# HIVE_BOARD_MCU.net
KiCad netlist of a schematic drawn in Altium Designer
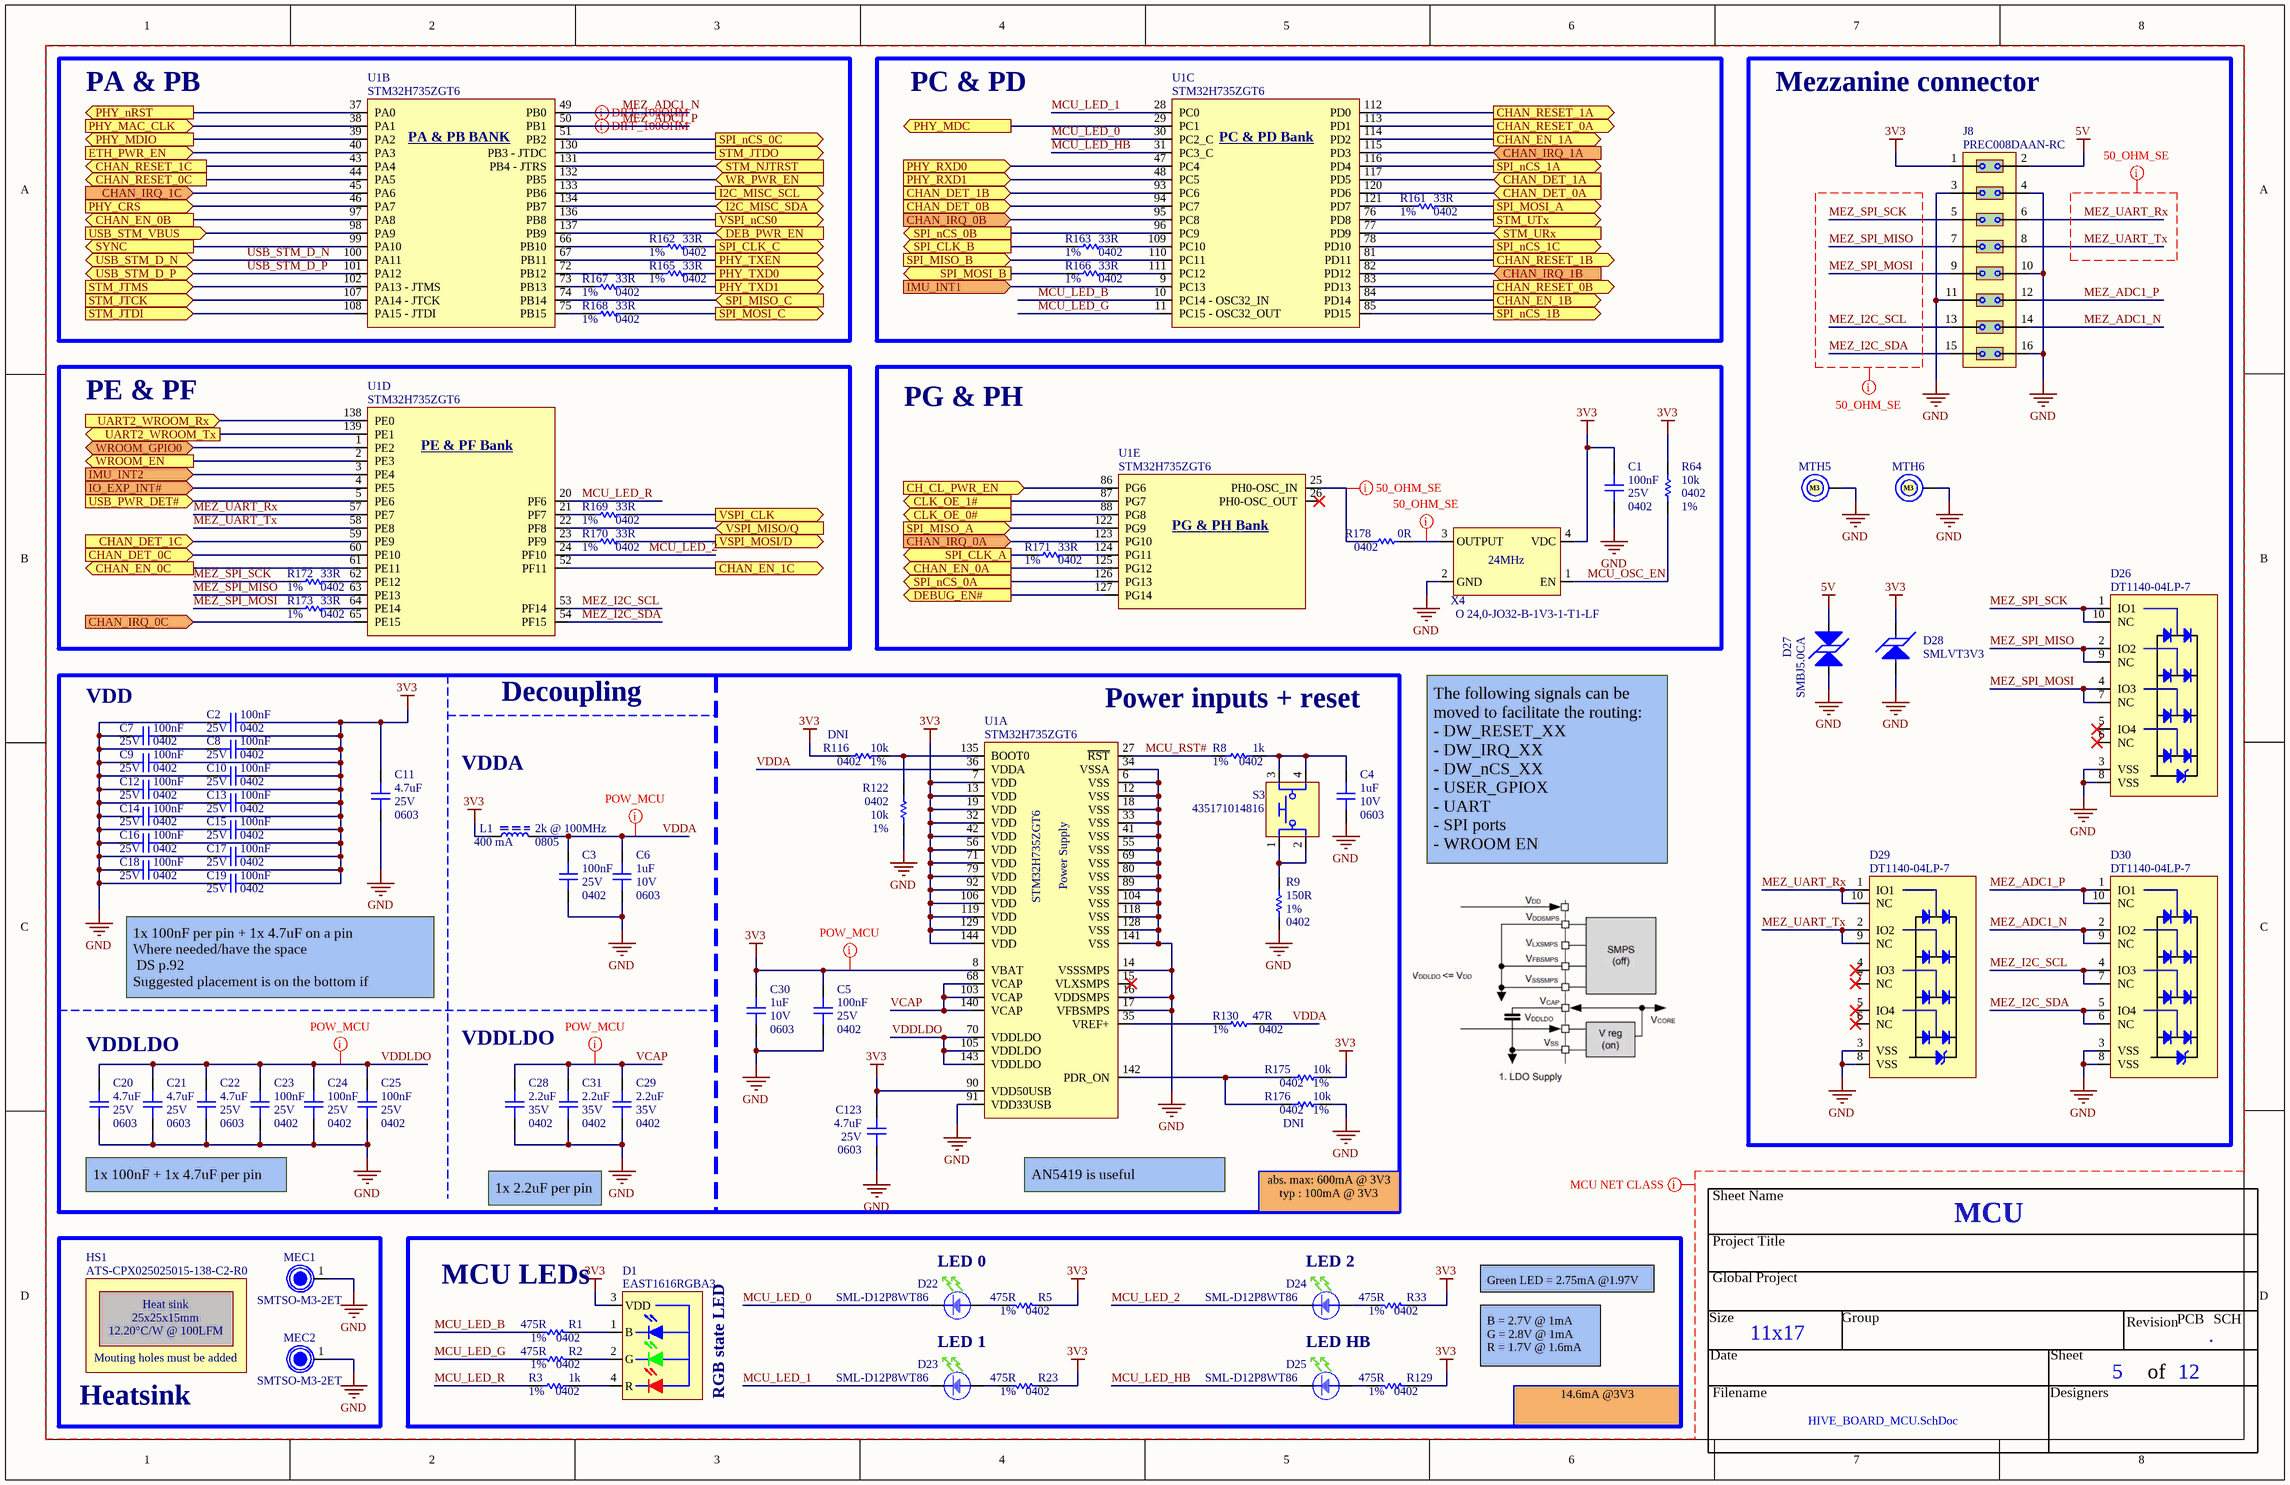
[diagram p0: HIVE_BOARD_MCU.SchDoc]

(export (version "E")
  (design (tool "Eeschema 10.0.6"))
  (components
    (comp (ref "C1")
      (value "100nF")
      (footprint "CAP_CER_0402")
      (description "CAP - CER 0.1µF 10% 25V X7R - 0402")
      (fields
        (field (name "TOLERANCE") "10%")
        (field (name "PACKAGE") "0402")
        (field (name "VOLTAGE RATING") "25V")
        (field (name "Comment") "CGA2B3X7R1E104K050BB")
        (field (name "CREATEDBY/DATE") "Nicolas Roy 2018-11-07")
        (field (name "VERIFIEDBY") "Nicolas V. (2019-01-22)")
      )
      (libsource (lib "GRAMS_MASTER_LIB") (part "CAP_CER_CGA2B3X7R1E104K050BB"))
    )
    (comp (ref "C2")
      (value "100nF")
      (footprint "CAP_CER_0402")
      (description "CAP - CER 0.1µF 10% 25V X7R - 0402")
      (fields
        (field (name "TOLERANCE") "10%")
        (field (name "PACKAGE") "0402")
        (field (name "VOLTAGE RATING") "25V")
        (field (name "Comment") "CGA2B3X7R1E104K050BB")
        (field (name "CREATEDBY/DATE") "Nicolas Roy 2018-11-07")
        (field (name "VERIFIEDBY") "Nicolas V. (2019-01-22)")
      )
      (libsource (lib "GRAMS_MASTER_LIB") (part "CAP_CER_CGA2B3X7R1E104K050BB"))
    )
    (comp (ref "C3")
      (value "100nF")
      (footprint "CAP_CER_0402")
      (description "CAP - CER 0.1µF 10% 25V X7R - 0402")
      (fields
        (field (name "TOLERANCE") "10%")
        (field (name "PACKAGE") "0402")
        (field (name "VOLTAGE RATING") "25V")
        (field (name "Comment") "CGA2B3X7R1E104K050BB")
        (field (name "CREATEDBY/DATE") "Nicolas Roy 2018-11-07")
        (field (name "VERIFIEDBY") "Nicolas V. (2019-01-22)")
      )
      (libsource (lib "GRAMS_MASTER_LIB") (part "CAP_CER_CGA2B3X7R1E104K050BB"))
    )
    (comp (ref "C4")
      (value "1uF")
      (footprint "CAP_CER_0603")
      (description "CAP - CER 1uF 10V 10% X5R - 0603")
      (fields
        (field (name "TOLERANCE") "10%")
        (field (name "PACKAGE") "0603")
        (field (name "VOLTAGE RATING") "10V")
        (field (name "Comment") "C0603C105K8PACTU")
        (field (name "CREATEDBY/DATE") "Hubert Dube - 21/07/20")
        (field (name "VERIFIEDBY") "Louis-Daniel Gaulin - 21/07/20")
      )
      (libsource (lib "SWARMUS_LIB") (part "CAP_CER_C0603C105K8PACTU"))
    )
    (comp (ref "C5")
      (value "100nF")
      (footprint "CAP_CER_0402")
      (description "CAP - CER 0.1µF 10% 25V X7R - 0402")
      (fields
        (field (name "TOLERANCE") "10%")
        (field (name "PACKAGE") "0402")
        (field (name "VOLTAGE RATING") "25V")
        (field (name "Comment") "CGA2B3X7R1E104K050BB")
        (field (name "CREATEDBY/DATE") "Nicolas Roy 2018-11-07")
        (field (name "VERIFIEDBY") "Nicolas V. (2019-01-22)")
      )
      (libsource (lib "GRAMS_MASTER_LIB") (part "CAP_CER_CGA2B3X7R1E104K050BB"))
    )
    (comp (ref "C6")
      (value "1uF")
      (footprint "CAP_CER_0603")
      (description "CAP - CER 1uF 10V 10% X5R - 0603")
      (fields
        (field (name "TOLERANCE") "10%")
        (field (name "PACKAGE") "0603")
        (field (name "VOLTAGE RATING") "10V")
        (field (name "Comment") "C0603C105K8PACTU")
        (field (name "CREATEDBY/DATE") "Hubert Dube - 21/07/20")
        (field (name "VERIFIEDBY") "Louis-Daniel Gaulin - 21/07/20")
      )
      (libsource (lib "SWARMUS_LIB") (part "CAP_CER_C0603C105K8PACTU"))
    )
    (comp (ref "C7")
      (value "100nF")
      (footprint "CAP_CER_0402")
      (description "CAP - CER 0.1µF 10% 25V X7R - 0402")
      (fields
        (field (name "TOLERANCE") "10%")
        (field (name "PACKAGE") "0402")
        (field (name "VOLTAGE RATING") "25V")
        (field (name "Comment") "CGA2B3X7R1E104K050BB")
        (field (name "CREATEDBY/DATE") "Nicolas Roy 2018-11-07")
        (field (name "VERIFIEDBY") "Nicolas V. (2019-01-22)")
      )
      (libsource (lib "GRAMS_MASTER_LIB") (part "CAP_CER_CGA2B3X7R1E104K050BB"))
    )
    (comp (ref "C8")
      (value "100nF")
      (footprint "CAP_CER_0402")
      (description "CAP - CER 0.1µF 10% 25V X7R - 0402")
      (fields
        (field (name "TOLERANCE") "10%")
        (field (name "PACKAGE") "0402")
        (field (name "VOLTAGE RATING") "25V")
        (field (name "Comment") "CGA2B3X7R1E104K050BB")
        (field (name "CREATEDBY/DATE") "Nicolas Roy 2018-11-07")
        (field (name "VERIFIEDBY") "Nicolas V. (2019-01-22)")
      )
      (libsource (lib "GRAMS_MASTER_LIB") (part "CAP_CER_CGA2B3X7R1E104K050BB"))
    )
    (comp (ref "C9")
      (value "100nF")
      (footprint "CAP_CER_0402")
      (description "CAP - CER 0.1µF 10% 25V X7R - 0402")
      (fields
        (field (name "TOLERANCE") "10%")
        (field (name "PACKAGE") "0402")
        (field (name "VOLTAGE RATING") "25V")
        (field (name "Comment") "CGA2B3X7R1E104K050BB")
        (field (name "CREATEDBY/DATE") "Nicolas Roy 2018-11-07")
        (field (name "VERIFIEDBY") "Nicolas V. (2019-01-22)")
      )
      (libsource (lib "GRAMS_MASTER_LIB") (part "CAP_CER_CGA2B3X7R1E104K050BB"))
    )
    (comp (ref "C10")
      (value "100nF")
      (footprint "CAP_CER_0402")
      (description "CAP - CER 0.1µF 10% 25V X7R - 0402")
      (fields
        (field (name "TOLERANCE") "10%")
        (field (name "PACKAGE") "0402")
        (field (name "VOLTAGE RATING") "25V")
        (field (name "Comment") "CGA2B3X7R1E104K050BB")
        (field (name "CREATEDBY/DATE") "Nicolas Roy 2018-11-07")
        (field (name "VERIFIEDBY") "Nicolas V. (2019-01-22)")
      )
      (libsource (lib "GRAMS_MASTER_LIB") (part "CAP_CER_CGA2B3X7R1E104K050BB"))
    )
    (comp (ref "C11")
      (value "4.7uF")
      (footprint "CAP_CER_0603")
      (description "CAP - CER 4.7µF 20% 25V X5R - 0603")
      (fields
        (field (name "TOLERANCE") "20%")
        (field (name "PACKAGE") "0603")
        (field (name "VOLTAGE RATING") "25V")
        (field (name "Comment") "CL10A475MA8NQNC")
        (field (name "CREATEDBY/DATE") "Nicolas Roy 2018-11-21")
        (field (name "VERIFIEDBY") "Nicolas V. (2019-01-22)")
      )
      (libsource (lib "GRAMS_MASTER_LIB") (part "CAP_CER_CL10A475MA8NQNC"))
    )
    (comp (ref "C12")
      (value "100nF")
      (footprint "CAP_CER_0402")
      (description "CAP - CER 0.1µF 10% 25V X7R - 0402")
      (fields
        (field (name "TOLERANCE") "10%")
        (field (name "PACKAGE") "0402")
        (field (name "VOLTAGE RATING") "25V")
        (field (name "Comment") "CGA2B3X7R1E104K050BB")
        (field (name "CREATEDBY/DATE") "Nicolas Roy 2018-11-07")
        (field (name "VERIFIEDBY") "Nicolas V. (2019-01-22)")
      )
      (libsource (lib "GRAMS_MASTER_LIB") (part "CAP_CER_CGA2B3X7R1E104K050BB"))
    )
    (comp (ref "C13")
      (value "100nF")
      (footprint "CAP_CER_0402")
      (description "CAP - CER 0.1µF 10% 25V X7R - 0402")
      (fields
        (field (name "TOLERANCE") "10%")
        (field (name "PACKAGE") "0402")
        (field (name "VOLTAGE RATING") "25V")
        (field (name "Comment") "CGA2B3X7R1E104K050BB")
        (field (name "CREATEDBY/DATE") "Nicolas Roy 2018-11-07")
        (field (name "VERIFIEDBY") "Nicolas V. (2019-01-22)")
      )
      (libsource (lib "GRAMS_MASTER_LIB") (part "CAP_CER_CGA2B3X7R1E104K050BB"))
    )
    (comp (ref "C14")
      (value "100nF")
      (footprint "CAP_CER_0402")
      (description "CAP - CER 0.1µF 10% 25V X7R - 0402")
      (fields
        (field (name "TOLERANCE") "10%")
        (field (name "PACKAGE") "0402")
        (field (name "VOLTAGE RATING") "25V")
        (field (name "Comment") "CGA2B3X7R1E104K050BB")
        (field (name "CREATEDBY/DATE") "Nicolas Roy 2018-11-07")
        (field (name "VERIFIEDBY") "Nicolas V. (2019-01-22)")
      )
      (libsource (lib "GRAMS_MASTER_LIB") (part "CAP_CER_CGA2B3X7R1E104K050BB"))
    )
    (comp (ref "C15")
      (value "100nF")
      (footprint "CAP_CER_0402")
      (description "CAP - CER 0.1µF 10% 25V X7R - 0402")
      (fields
        (field (name "TOLERANCE") "10%")
        (field (name "PACKAGE") "0402")
        (field (name "VOLTAGE RATING") "25V")
        (field (name "Comment") "CGA2B3X7R1E104K050BB")
        (field (name "CREATEDBY/DATE") "Nicolas Roy 2018-11-07")
        (field (name "VERIFIEDBY") "Nicolas V. (2019-01-22)")
      )
      (libsource (lib "GRAMS_MASTER_LIB") (part "CAP_CER_CGA2B3X7R1E104K050BB"))
    )
    (comp (ref "C16")
      (value "100nF")
      (footprint "CAP_CER_0402")
      (description "CAP - CER 0.1µF 10% 25V X7R - 0402")
      (fields
        (field (name "TOLERANCE") "10%")
        (field (name "PACKAGE") "0402")
        (field (name "VOLTAGE RATING") "25V")
        (field (name "Comment") "CGA2B3X7R1E104K050BB")
        (field (name "CREATEDBY/DATE") "Nicolas Roy 2018-11-07")
        (field (name "VERIFIEDBY") "Nicolas V. (2019-01-22)")
      )
      (libsource (lib "GRAMS_MASTER_LIB") (part "CAP_CER_CGA2B3X7R1E104K050BB"))
    )
    (comp (ref "C17")
      (value "100nF")
      (footprint "CAP_CER_0402")
      (description "CAP - CER 0.1µF 10% 25V X7R - 0402")
      (fields
        (field (name "TOLERANCE") "10%")
        (field (name "PACKAGE") "0402")
        (field (name "VOLTAGE RATING") "25V")
        (field (name "Comment") "CGA2B3X7R1E104K050BB")
        (field (name "CREATEDBY/DATE") "Nicolas Roy 2018-11-07")
        (field (name "VERIFIEDBY") "Nicolas V. (2019-01-22)")
      )
      (libsource (lib "GRAMS_MASTER_LIB") (part "CAP_CER_CGA2B3X7R1E104K050BB"))
    )
    (comp (ref "C18")
      (value "100nF")
      (footprint "CAP_CER_0402")
      (description "CAP - CER 0.1µF 10% 25V X7R - 0402")
      (fields
        (field (name "TOLERANCE") "10%")
        (field (name "PACKAGE") "0402")
        (field (name "VOLTAGE RATING") "25V")
        (field (name "Comment") "CGA2B3X7R1E104K050BB")
        (field (name "CREATEDBY/DATE") "Nicolas Roy 2018-11-07")
        (field (name "VERIFIEDBY") "Nicolas V. (2019-01-22)")
      )
      (libsource (lib "GRAMS_MASTER_LIB") (part "CAP_CER_CGA2B3X7R1E104K050BB"))
    )
    (comp (ref "C19")
      (value "100nF")
      (footprint "CAP_CER_0402")
      (description "CAP - CER 0.1µF 10% 25V X7R - 0402")
      (fields
        (field (name "TOLERANCE") "10%")
        (field (name "PACKAGE") "0402")
        (field (name "VOLTAGE RATING") "25V")
        (field (name "Comment") "CGA2B3X7R1E104K050BB")
        (field (name "CREATEDBY/DATE") "Nicolas Roy 2018-11-07")
        (field (name "VERIFIEDBY") "Nicolas V. (2019-01-22)")
      )
      (libsource (lib "GRAMS_MASTER_LIB") (part "CAP_CER_CGA2B3X7R1E104K050BB"))
    )
    (comp (ref "C20")
      (value "4.7uF")
      (footprint "CAP_CER_0603")
      (description "CAP - CER 4.7µF 20% 25V X5R - 0603")
      (fields
        (field (name "TOLERANCE") "20%")
        (field (name "PACKAGE") "0603")
        (field (name "VOLTAGE RATING") "25V")
        (field (name "Comment") "CL10A475MA8NQNC")
        (field (name "CREATEDBY/DATE") "Nicolas Roy 2018-11-21")
        (field (name "VERIFIEDBY") "Nicolas V. (2019-01-22)")
      )
      (libsource (lib "GRAMS_MASTER_LIB") (part "CAP_CER_CL10A475MA8NQNC"))
    )
    (comp (ref "C21")
      (value "4.7uF")
      (footprint "CAP_CER_0603")
      (description "CAP - CER 4.7µF 20% 25V X5R - 0603")
      (fields
        (field (name "TOLERANCE") "20%")
        (field (name "PACKAGE") "0603")
        (field (name "VOLTAGE RATING") "25V")
        (field (name "Comment") "CL10A475MA8NQNC")
        (field (name "CREATEDBY/DATE") "Nicolas Roy 2018-11-21")
        (field (name "VERIFIEDBY") "Nicolas V. (2019-01-22)")
      )
      (libsource (lib "GRAMS_MASTER_LIB") (part "CAP_CER_CL10A475MA8NQNC"))
    )
    (comp (ref "C22")
      (value "4.7uF")
      (footprint "CAP_CER_0603")
      (description "CAP - CER 4.7µF 20% 25V X5R - 0603")
      (fields
        (field (name "TOLERANCE") "20%")
        (field (name "PACKAGE") "0603")
        (field (name "VOLTAGE RATING") "25V")
        (field (name "Comment") "CL10A475MA8NQNC")
        (field (name "CREATEDBY/DATE") "Nicolas Roy 2018-11-21")
        (field (name "VERIFIEDBY") "Nicolas V. (2019-01-22)")
      )
      (libsource (lib "GRAMS_MASTER_LIB") (part "CAP_CER_CL10A475MA8NQNC"))
    )
    (comp (ref "C23")
      (value "100nF")
      (footprint "CAP_CER_0402")
      (description "CAP - CER 0.1µF 10% 25V X7R - 0402")
      (fields
        (field (name "TOLERANCE") "10%")
        (field (name "PACKAGE") "0402")
        (field (name "VOLTAGE RATING") "25V")
        (field (name "Comment") "CGA2B3X7R1E104K050BB")
        (field (name "CREATEDBY/DATE") "Nicolas Roy 2018-11-07")
        (field (name "VERIFIEDBY") "Nicolas V. (2019-01-22)")
      )
      (libsource (lib "GRAMS_MASTER_LIB") (part "CAP_CER_CGA2B3X7R1E104K050BB"))
    )
    (comp (ref "C24")
      (value "100nF")
      (footprint "CAP_CER_0402")
      (description "CAP - CER 0.1µF 10% 25V X7R - 0402")
      (fields
        (field (name "TOLERANCE") "10%")
        (field (name "PACKAGE") "0402")
        (field (name "VOLTAGE RATING") "25V")
        (field (name "Comment") "CGA2B3X7R1E104K050BB")
        (field (name "CREATEDBY/DATE") "Nicolas Roy 2018-11-07")
        (field (name "VERIFIEDBY") "Nicolas V. (2019-01-22)")
      )
      (libsource (lib "GRAMS_MASTER_LIB") (part "CAP_CER_CGA2B3X7R1E104K050BB"))
    )
    (comp (ref "C25")
      (value "100nF")
      (footprint "CAP_CER_0402")
      (description "CAP - CER 0.1µF 10% 25V X7R - 0402")
      (fields
        (field (name "TOLERANCE") "10%")
        (field (name "PACKAGE") "0402")
        (field (name "VOLTAGE RATING") "25V")
        (field (name "Comment") "CGA2B3X7R1E104K050BB")
        (field (name "CREATEDBY/DATE") "Nicolas Roy 2018-11-07")
        (field (name "VERIFIEDBY") "Nicolas V. (2019-01-22)")
      )
      (libsource (lib "GRAMS_MASTER_LIB") (part "CAP_CER_CGA2B3X7R1E104K050BB"))
    )
    (comp (ref "C28")
      (value "2.2uF")
      (footprint "CAP_CER_0402")
      (description "CAP - CER 2.2µF 10% 35V X5R - 0402")
      (fields
        (field (name "TOLERANCE") "10%")
        (field (name "PACKAGE") "0402")
        (field (name "VOLTAGE RATING") "35V")
        (field (name "Comment") "C1005X5R1V225K050BC")
        (field (name "CREATEDBY/DATE") "Nicolas Roy 2018-10-17")
        (field (name "VERIFIEDBY") "Caroline Paulin - 18 janv 2018")
      )
      (libsource (lib "GRAMS_MASTER_LIB") (part "CAP_CER_C1005X5R1V225K050BC"))
    )
    (comp (ref "C29")
      (value "2.2uF")
      (footprint "CAP_CER_0402")
      (description "CAP - CER 2.2µF 10% 35V X5R - 0402")
      (fields
        (field (name "TOLERANCE") "10%")
        (field (name "PACKAGE") "0402")
        (field (name "VOLTAGE RATING") "35V")
        (field (name "Comment") "C1005X5R1V225K050BC")
        (field (name "CREATEDBY/DATE") "Nicolas Roy 2018-10-17")
        (field (name "VERIFIEDBY") "Caroline Paulin - 18 janv 2018")
      )
      (libsource (lib "GRAMS_MASTER_LIB") (part "CAP_CER_C1005X5R1V225K050BC"))
    )
    (comp (ref "C30")
      (value "1uF")
      (footprint "CAP_CER_0603")
      (description "CAP - CER 1uF 10V 10% X5R - 0603")
      (fields
        (field (name "TOLERANCE") "10%")
        (field (name "PACKAGE") "0603")
        (field (name "VOLTAGE RATING") "10V")
        (field (name "Comment") "C0603C105K8PACTU")
        (field (name "CREATEDBY/DATE") "Hubert Dube - 21/07/20")
        (field (name "VERIFIEDBY") "Louis-Daniel Gaulin - 21/07/20")
      )
      (libsource (lib "SWARMUS_LIB") (part "CAP_CER_C0603C105K8PACTU"))
    )
    (comp (ref "C31")
      (value "2.2uF")
      (footprint "CAP_CER_0402")
      (description "CAP - CER 2.2µF 10% 35V X5R - 0402")
      (fields
        (field (name "TOLERANCE") "10%")
        (field (name "PACKAGE") "0402")
        (field (name "VOLTAGE RATING") "35V")
        (field (name "Comment") "C1005X5R1V225K050BC")
        (field (name "CREATEDBY/DATE") "Nicolas Roy 2018-10-17")
        (field (name "VERIFIEDBY") "Caroline Paulin - 18 janv 2018")
      )
      (libsource (lib "GRAMS_MASTER_LIB") (part "CAP_CER_C1005X5R1V225K050BC"))
    )
    (comp (ref "C123")
      (value "4.7uF")
      (footprint "CAP_CER_0603")
      (description "CAP - CER 4.7µF 20% 25V X5R - 0603")
      (fields
        (field (name "TOLERANCE") "20%")
        (field (name "PACKAGE") "0603")
        (field (name "VOLTAGE RATING") "25V")
        (field (name "Comment") "CL10A475MA8NQNC")
        (field (name "CREATEDBY/DATE") "Nicolas Roy 2018-11-21")
        (field (name "VERIFIEDBY") "Nicolas V. (2019-01-22)")
      )
      (libsource (lib "GRAMS_MASTER_LIB") (part "CAP_CER_CL10A475MA8NQNC"))
    )
    (comp (ref "D1")
      (value "EAST1616RGBA3")
      (footprint "DIO_EAST1616RGBA3")
      (fields
        (field (name "TOLERANCE") "±50ppm")
        (field (name "CREATEDBY/DATE") "Hubert Dube - 26/02/2021")
        (field (name "VERIFIEDBY") "PA + Hubert Dube - 19/03/2021")
      )
      (libsource (lib "SWARMUS_LIB") (part "DIO_EAST1616RGBA3"))
    )
    (comp (ref "D22")
      (value "SML-D12P8WT86")
      (footprint "LED_SML-D12P8WT86")
      (description "LED - GREEN DIFFUSED 0603 SMD - 0603")
      (fields
        (field (name "CREATEDBY/DATE") "Keven Deslandes - 2018/11/21")
        (field (name "VERIFIEDBY") "Caroline Paulin - 13 février 2019")
      )
      (libsource (lib "GRAMS_MASTER_LIB") (part "LED_SML-D12P8WT86"))
    )
    (comp (ref "D23")
      (value "SML-D12P8WT86")
      (footprint "LED_SML-D12P8WT86")
      (description "LED - GREEN DIFFUSED 0603 SMD - 0603")
      (fields
        (field (name "CREATEDBY/DATE") "Keven Deslandes - 2018/11/21")
        (field (name "VERIFIEDBY") "Caroline Paulin - 13 février 2019")
      )
      (libsource (lib "GRAMS_MASTER_LIB") (part "LED_SML-D12P8WT86"))
    )
    (comp (ref "D24")
      (value "SML-D12P8WT86")
      (footprint "LED_SML-D12P8WT86")
      (description "LED - GREEN DIFFUSED 0603 SMD - 0603")
      (fields
        (field (name "CREATEDBY/DATE") "Keven Deslandes - 2018/11/21")
        (field (name "VERIFIEDBY") "Caroline Paulin - 13 février 2019")
      )
      (libsource (lib "GRAMS_MASTER_LIB") (part "LED_SML-D12P8WT86"))
    )
    (comp (ref "D25")
      (value "SML-D12P8WT86")
      (footprint "LED_SML-D12P8WT86")
      (description "LED - GREEN DIFFUSED 0603 SMD - 0603")
      (fields
        (field (name "CREATEDBY/DATE") "Keven Deslandes - 2018/11/21")
        (field (name "VERIFIEDBY") "Caroline Paulin - 13 février 2019")
      )
      (libsource (lib "GRAMS_MASTER_LIB") (part "LED_SML-D12P8WT86"))
    )
    (comp (ref "D26")
      (value "DT1140-04LP-7")
      (footprint "TVS_DATA_DT1140-04LP-7")
      (description "TVS - DIODE 5.5V 10V - 10-UFDFN")
      (fields
        (field (name "CREATEDBY/DATE") "Joël Lemay 2019-11-20")
        (field (name "VERIFIEDBY") "C.Paulin - 21/11/2019")
      )
      (libsource (lib "GRAMS_MASTER_LIB") (part "TVS_DATA_DT1140-04LP-7"))
    )
    (comp (ref "D27")
      (value "SMBJ5.0CA")
      (footprint "TVS_PWR_SMBJ5.0CA")
      (description "TVS - BIDIR 5V 9.2V 600W - DO214AA")
      (fields
        (field (name "CREATEDBY/DATE") "Jonathan Bouchard - 2019-03-22")
        (field (name "VERIFIEDBY") "Nicolas V. (2019-05-06)")
      )
      (libsource (lib "GRAMS_MASTER_LIB") (part "TVS_PWR_SMBJ5.0CA"))
    )
    (comp (ref "D28")
      (value "SMLVT3V3")
      (footprint "TVS_POW_SMLVT3V3")
      (description "TVS - 3.3V 10.3V 600W - DO214AA")
      (fields
        (field (name "CREATEDBY/DATE") "Jonathan Bouchard - 2019-04-27")
        (field (name "VERIFIEDBY") "Nicolas V. (2019-05-06)")
      )
      (libsource (lib "GRAMS_MASTER_LIB") (part "TVS_POW_SMLVT3V3"))
    )
    (comp (ref "D29")
      (value "DT1140-04LP-7")
      (footprint "TVS_DATA_DT1140-04LP-7")
      (description "TVS - DIODE 5.5V 10V - 10-UFDFN")
      (fields
        (field (name "CREATEDBY/DATE") "Joël Lemay 2019-11-20")
        (field (name "VERIFIEDBY") "C.Paulin - 21/11/2019")
      )
      (libsource (lib "GRAMS_MASTER_LIB") (part "TVS_DATA_DT1140-04LP-7"))
    )
    (comp (ref "D30")
      (value "DT1140-04LP-7")
      (footprint "TVS_DATA_DT1140-04LP-7")
      (description "TVS - DIODE 5.5V 10V - 10-UFDFN")
      (fields
        (field (name "CREATEDBY/DATE") "Joël Lemay 2019-11-20")
        (field (name "VERIFIEDBY") "C.Paulin - 21/11/2019")
      )
      (libsource (lib "GRAMS_MASTER_LIB") (part "TVS_DATA_DT1140-04LP-7"))
    )
    (comp (ref "HS1")
      (value "ATS-CPX025025015-138-C2-R0")
      (footprint "THE_HS_ATS-CPX025025015-138-C2-R0_NOMH")
      (description "THE_HS - Heat Sink  25x25x15 mm - TH M3")
      (fields
        (field (name "CREATEDBY/DATE") "Philippe Arsenault/2021-04-08")
        (field (name "VERIFIEDBY") "Louis-Daniel Gaulin / 14-04-2021")
      )
      (libsource (lib "SWARMUS_LIB") (part "THE_HS_ATS-CPX025025015-138-C2-R0_NOMH"))
    )
    (comp (ref "J8")
      (value "PREC008DAAN-RC")
      (footprint "CON_HDR_PREC008DAAN-RC")
      (description "CON - Connector Header Through Hole 16 position 0.100\" (2.54mm)")
      (fields
        (field (name "VERIFIEDBY") "Philippe Arsenault/2021-03-25")
        (field (name "CREATEDBY/DATE") "Hubert Dube -  16/03/2021")
      )
      (libsource (lib "SWARMUS_LIB") (part "CON_HDR_PREC008DAAN-RC"))
    )
    (comp (ref "L1")
      (value "2k @ 100MHz")
      (footprint "FER_0805")
      (description "FER - FERRITE BEAD 2 KOHM @ 100 MHz 400 mA - 0805")
      (fields
        (field (name "CURRENT RATING") "400 mA")
        (field (name "PACKAGE") "0805")
        (field (name "Comment") "MMZ2012Y202BT000")
        (field (name "CREATEDBY/DATE") "Hubert Dube - 7/02/2021")
        (field (name "VERIFIEDBY") "Philippe Arsenault/ 2021-03-13")
      )
      (libsource (lib "SWARMUS_LIB") (part "FER_MMZ2012Y202BT000"))
    )
    (comp (ref "MEC1")
      (value "SMTSO-M3-2ET")
      (footprint "MEC_PEM_SMTSO-M3-2ET")
      (description "MEC- PEM SMD THREADED SPACER M3 - SMD")
      (fields
        (field (name "CREATEDBY/DATE") "Gabriel St-H./30-04-2019")
        (field (name "VERIFIEDBY") "Nicolas V. (2019-05-02)")
      )
      (libsource (lib "GRAMS_MASTER_LIB") (part "MEC_PEM_SMTSO-M3-2ET"))
    )
    (comp (ref "MEC2")
      (value "SMTSO-M3-2ET")
      (footprint "MEC_PEM_SMTSO-M3-2ET")
      (description "MEC- PEM SMD THREADED SPACER M3 - SMD")
      (fields
        (field (name "CREATEDBY/DATE") "Gabriel St-H./30-04-2019")
        (field (name "VERIFIEDBY") "Nicolas V. (2019-05-02)")
      )
      (libsource (lib "GRAMS_MASTER_LIB") (part "MEC_PEM_SMTSO-M3-2ET"))
    )
    (comp (ref "MTH5")
      (value "M3")
      (footprint "MTH_M3")
      (description "MTH - MOUNTING HOLE M3 PLATED - M3")
      (fields
        (field (name "CREATEDBY/DATE") "Jonathan Bouchard 2018-07-23")
        (field (name "VERIFIEDBY") "Arnaud Samson 23-07-18")
      )
      (libsource (lib "GRAMS_MASTER_LIB") (part "MTH_M3"))
    )
    (comp (ref "MTH6")
      (value "M3")
      (footprint "MTH_M3")
      (description "MTH - MOUNTING HOLE M3 PLATED - M3")
      (fields
        (field (name "CREATEDBY/DATE") "Jonathan Bouchard 2018-07-23")
        (field (name "VERIFIEDBY") "Arnaud Samson 23-07-18")
      )
      (libsource (lib "GRAMS_MASTER_LIB") (part "MTH_M3"))
    )
    (comp (ref "R1")
      (value "475R")
      (footprint "RES_0402")
      (description "RES - 475R 1% 1/10W- 0402")
      (fields
        (field (name "TOLERANCE") "1%")
        (field (name "PACKAGE") "0402")
        (field (name "Comment") "ERJ-2RKF4750X")
        (field (name "CREATEDBY/DATE") "Keven Deslandes 2018-10-17")
        (field (name "VERIFIEDBY") "Carolilne Paulin - 18/12/2018")
      )
      (libsource (lib "GRAMS_MASTER_LIB") (part "RES_ERJ-2RKF4750X"))
    )
    (comp (ref "R2")
      (value "475R")
      (footprint "RES_0402")
      (description "RES - 475R 1% 1/10W- 0402")
      (fields
        (field (name "TOLERANCE") "1%")
        (field (name "PACKAGE") "0402")
        (field (name "Comment") "ERJ-2RKF4750X")
        (field (name "CREATEDBY/DATE") "Keven Deslandes 2018-10-17")
        (field (name "VERIFIEDBY") "Carolilne Paulin - 18/12/2018")
      )
      (libsource (lib "GRAMS_MASTER_LIB") (part "RES_ERJ-2RKF4750X"))
    )
    (comp (ref "R3")
      (value "1k")
      (footprint "RES_0402")
      (description "RES - 1K OHM 1% 1/16W - 0402")
      (fields
        (field (name "TOLERANCE") "1%")
        (field (name "PACKAGE") "0402")
        (field (name "Comment") "RC0402FR-071KL")
        (field (name "CREATEDBY/DATE") "Jonathan Bouchard 2018-07-05")
        (field (name "VERIFIEDBY") "Arnaud Samson 16-07-18")
      )
      (libsource (lib "GRAMS_MASTER_LIB") (part "RES_RC0402FR-071KL"))
    )
    (comp (ref "R5")
      (value "475R")
      (footprint "RES_0402")
      (description "RES - 475R 1% 1/10W- 0402")
      (fields
        (field (name "TOLERANCE") "1%")
        (field (name "PACKAGE") "0402")
        (field (name "Comment") "ERJ-2RKF4750X")
        (field (name "CREATEDBY/DATE") "Keven Deslandes 2018-10-17")
        (field (name "VERIFIEDBY") "Carolilne Paulin - 18/12/2018")
      )
      (libsource (lib "GRAMS_MASTER_LIB") (part "RES_ERJ-2RKF4750X"))
    )
    (comp (ref "R8")
      (value "1k")
      (footprint "RES_0402")
      (description "RES - 1K OHM 1% 1/16W - 0402")
      (fields
        (field (name "TOLERANCE") "1%")
        (field (name "PACKAGE") "0402")
        (field (name "Comment") "RC0402FR-071KL")
        (field (name "CREATEDBY/DATE") "Jonathan Bouchard 2018-07-05")
        (field (name "VERIFIEDBY") "Arnaud Samson 16-07-18")
      )
      (libsource (lib "GRAMS_MASTER_LIB") (part "RES_RC0402FR-071KL"))
    )
    (comp (ref "R9")
      (value "150R")
      (footprint "RES_0402")
      (description "RES - 150R 1% 1/16W - 0402")
      (fields
        (field (name "TOLERANCE") "1%")
        (field (name "PACKAGE") "0402")
        (field (name "Comment") "RC0402FR-07150RL")
        (field (name "CREATEDBY/DATE") "Jonathan Bouchard 2019-03-25")
        (field (name "VERIFIEDBY") "Nicolas V. (2019-05-02)")
      )
      (libsource (lib "GRAMS_MASTER_LIB") (part "RES_RC0402FR-07150RL"))
    )
    (comp (ref "R23")
      (value "475R")
      (footprint "RES_0402")
      (description "RES - 475R 1% 1/10W- 0402")
      (fields
        (field (name "TOLERANCE") "1%")
        (field (name "PACKAGE") "0402")
        (field (name "Comment") "ERJ-2RKF4750X")
        (field (name "CREATEDBY/DATE") "Keven Deslandes 2018-10-17")
        (field (name "VERIFIEDBY") "Carolilne Paulin - 18/12/2018")
      )
      (libsource (lib "GRAMS_MASTER_LIB") (part "RES_ERJ-2RKF4750X"))
    )
    (comp (ref "R33")
      (value "475R")
      (footprint "RES_0402")
      (description "RES - 475R 1% 1/10W- 0402")
      (fields
        (field (name "TOLERANCE") "1%")
        (field (name "PACKAGE") "0402")
        (field (name "Comment") "ERJ-2RKF4750X")
        (field (name "CREATEDBY/DATE") "Keven Deslandes 2018-10-17")
        (field (name "VERIFIEDBY") "Carolilne Paulin - 18/12/2018")
      )
      (libsource (lib "GRAMS_MASTER_LIB") (part "RES_ERJ-2RKF4750X"))
    )
    (comp (ref "R64")
      (value "10k")
      (footprint "RES_0402")
      (description "RES - 10K OHMS 1% 1/16W - 0402")
      (fields
        (field (name "TOLERANCE") "1%")
        (field (name "PACKAGE") "0402")
        (field (name "Comment") "RC0402FR-0710KL")
        (field (name "CREATEDBY/DATE") "Nicolas V. (2018-11-20)")
        (field (name "VERIFIEDBY") "Nicolas V. (2018-11-20)")
      )
      (libsource (lib "GRAMS_MASTER_LIB") (part "RES_RC0402FR-0710KL"))
    )
    (comp (ref "R116")
      (value "10k")
      (footprint "RES_0402")
      (description "RES - 10K OHMS 1% 1/16W - 0402")
      (fields
        (field (name "TOLERANCE") "1%")
        (field (name "ASSEMBLY NOTE") "DNI")
        (field (name "PACKAGE") "0402")
        (field (name "Comment") "RC0402FR-0710KL")
        (field (name "CREATEDBY/DATE") "Nicolas V. (2018-11-20)")
        (field (name "VERIFIEDBY") "Nicolas V. (2018-11-20)")
      )
      (libsource (lib "GRAMS_MASTER_LIB") (part "RES_RC0402FR-0710KL"))
    )
    (comp (ref "R122")
      (value "10k")
      (footprint "RES_0402")
      (description "RES - 10K OHMS 1% 1/16W - 0402")
      (fields
        (field (name "TOLERANCE") "1%")
        (field (name "PACKAGE") "0402")
        (field (name "Comment") "RC0402FR-0710KL")
        (field (name "CREATEDBY/DATE") "Nicolas V. (2018-11-20)")
        (field (name "VERIFIEDBY") "Nicolas V. (2018-11-20)")
      )
      (libsource (lib "GRAMS_MASTER_LIB") (part "RES_RC0402FR-0710KL"))
    )
    (comp (ref "R129")
      (value "475R")
      (footprint "RES_0402")
      (description "RES - 475R 1% 1/10W- 0402")
      (fields
        (field (name "TOLERANCE") "1%")
        (field (name "PACKAGE") "0402")
        (field (name "Comment") "ERJ-2RKF4750X")
        (field (name "CREATEDBY/DATE") "Keven Deslandes 2018-10-17")
        (field (name "VERIFIEDBY") "Carolilne Paulin - 18/12/2018")
      )
      (libsource (lib "GRAMS_MASTER_LIB") (part "RES_ERJ-2RKF4750X"))
    )
    (comp (ref "R130")
      (value "47R")
      (footprint "RES_0402")
      (description "RES -  47ohm ±1% 0.063W, 1/16W Chip Resistor 0402")
      (fields
        (field (name "TOLERANCE") "1%")
        (field (name "PACKAGE") "0402")
        (field (name "Comment") "RC0402FR-0747RL")
        (field (name "CREATEDBY/DATE") "Philippe Arsenault/2021-04-10")
        (field (name "VERIFIEDBY") "Louis-Daniel Gaulin / 14-04-2021")
      )
      (libsource (lib "SWARMUS_LIB") (part "RES_RC0402FR-0747RL"))
    )
    (comp (ref "R161")
      (value "33R")
      (footprint "RES_0402")
      (description "RES - 33 OHM 1% 1/16W - 0402")
      (fields
        (field (name "TOLERANCE") "1%")
        (field (name "PACKAGE") "0402")
        (field (name "Comment") "RC0402FR-0733RL")
        (field (name "CREATEDBY/DATE") "Louis-Daniel Gaulin/ 14/01/2020")
        (field (name "VERIFIEDBY") "C.Paulin - 21/01/2020")
      )
      (libsource (lib "GRAMS_MASTER_LIB") (part "RES_RC0402FR-0733RL"))
    )
    (comp (ref "R162")
      (value "33R")
      (footprint "RES_0402")
      (description "RES - 33 OHM 1% 1/16W - 0402")
      (fields
        (field (name "TOLERANCE") "1%")
        (field (name "PACKAGE") "0402")
        (field (name "Comment") "RC0402FR-0733RL")
        (field (name "CREATEDBY/DATE") "Louis-Daniel Gaulin/ 14/01/2020")
        (field (name "VERIFIEDBY") "C.Paulin - 21/01/2020")
      )
      (libsource (lib "GRAMS_MASTER_LIB") (part "RES_RC0402FR-0733RL"))
    )
    (comp (ref "R163")
      (value "33R")
      (footprint "RES_0402")
      (description "RES - 33 OHM 1% 1/16W - 0402")
      (fields
        (field (name "TOLERANCE") "1%")
        (field (name "PACKAGE") "0402")
        (field (name "Comment") "RC0402FR-0733RL")
        (field (name "CREATEDBY/DATE") "Louis-Daniel Gaulin/ 14/01/2020")
        (field (name "VERIFIEDBY") "C.Paulin - 21/01/2020")
      )
      (libsource (lib "GRAMS_MASTER_LIB") (part "RES_RC0402FR-0733RL"))
    )
    (comp (ref "R165")
      (value "33R")
      (footprint "RES_0402")
      (description "RES - 33 OHM 1% 1/16W - 0402")
      (fields
        (field (name "TOLERANCE") "1%")
        (field (name "PACKAGE") "0402")
        (field (name "Comment") "RC0402FR-0733RL")
        (field (name "CREATEDBY/DATE") "Louis-Daniel Gaulin/ 14/01/2020")
        (field (name "VERIFIEDBY") "C.Paulin - 21/01/2020")
      )
      (libsource (lib "GRAMS_MASTER_LIB") (part "RES_RC0402FR-0733RL"))
    )
    (comp (ref "R166")
      (value "33R")
      (footprint "RES_0402")
      (description "RES - 33 OHM 1% 1/16W - 0402")
      (fields
        (field (name "TOLERANCE") "1%")
        (field (name "PACKAGE") "0402")
        (field (name "Comment") "RC0402FR-0733RL")
        (field (name "CREATEDBY/DATE") "Louis-Daniel Gaulin/ 14/01/2020")
        (field (name "VERIFIEDBY") "C.Paulin - 21/01/2020")
      )
      (libsource (lib "GRAMS_MASTER_LIB") (part "RES_RC0402FR-0733RL"))
    )
    (comp (ref "R167")
      (value "33R")
      (footprint "RES_0402")
      (description "RES - 33 OHM 1% 1/16W - 0402")
      (fields
        (field (name "TOLERANCE") "1%")
        (field (name "PACKAGE") "0402")
        (field (name "Comment") "RC0402FR-0733RL")
        (field (name "CREATEDBY/DATE") "Louis-Daniel Gaulin/ 14/01/2020")
        (field (name "VERIFIEDBY") "C.Paulin - 21/01/2020")
      )
      (libsource (lib "GRAMS_MASTER_LIB") (part "RES_RC0402FR-0733RL"))
    )
    (comp (ref "R168")
      (value "33R")
      (footprint "RES_0402")
      (description "RES - 33 OHM 1% 1/16W - 0402")
      (fields
        (field (name "TOLERANCE") "1%")
        (field (name "PACKAGE") "0402")
        (field (name "Comment") "RC0402FR-0733RL")
        (field (name "CREATEDBY/DATE") "Louis-Daniel Gaulin/ 14/01/2020")
        (field (name "VERIFIEDBY") "C.Paulin - 21/01/2020")
      )
      (libsource (lib "GRAMS_MASTER_LIB") (part "RES_RC0402FR-0733RL"))
    )
    (comp (ref "R169")
      (value "33R")
      (footprint "RES_0402")
      (description "RES - 33 OHM 1% 1/16W - 0402")
      (fields
        (field (name "TOLERANCE") "1%")
        (field (name "PACKAGE") "0402")
        (field (name "Comment") "RC0402FR-0733RL")
        (field (name "CREATEDBY/DATE") "Louis-Daniel Gaulin/ 14/01/2020")
        (field (name "VERIFIEDBY") "C.Paulin - 21/01/2020")
      )
      (libsource (lib "GRAMS_MASTER_LIB") (part "RES_RC0402FR-0733RL"))
    )
    (comp (ref "R170")
      (value "33R")
      (footprint "RES_0402")
      (description "RES - 33 OHM 1% 1/16W - 0402")
      (fields
        (field (name "TOLERANCE") "1%")
        (field (name "PACKAGE") "0402")
        (field (name "Comment") "RC0402FR-0733RL")
        (field (name "CREATEDBY/DATE") "Louis-Daniel Gaulin/ 14/01/2020")
        (field (name "VERIFIEDBY") "C.Paulin - 21/01/2020")
      )
      (libsource (lib "GRAMS_MASTER_LIB") (part "RES_RC0402FR-0733RL"))
    )
    (comp (ref "R171")
      (value "33R")
      (footprint "RES_0402")
      (description "RES - 33 OHM 1% 1/16W - 0402")
      (fields
        (field (name "TOLERANCE") "1%")
        (field (name "PACKAGE") "0402")
        (field (name "Comment") "RC0402FR-0733RL")
        (field (name "CREATEDBY/DATE") "Louis-Daniel Gaulin/ 14/01/2020")
        (field (name "VERIFIEDBY") "C.Paulin - 21/01/2020")
      )
      (libsource (lib "GRAMS_MASTER_LIB") (part "RES_RC0402FR-0733RL"))
    )
    (comp (ref "R172")
      (value "33R")
      (footprint "RES_0402")
      (description "RES - 33 OHM 1% 1/16W - 0402")
      (fields
        (field (name "TOLERANCE") "1%")
        (field (name "PACKAGE") "0402")
        (field (name "Comment") "RC0402FR-0733RL")
        (field (name "CREATEDBY/DATE") "Louis-Daniel Gaulin/ 14/01/2020")
        (field (name "VERIFIEDBY") "C.Paulin - 21/01/2020")
      )
      (libsource (lib "GRAMS_MASTER_LIB") (part "RES_RC0402FR-0733RL"))
    )
    (comp (ref "R173")
      (value "33R")
      (footprint "RES_0402")
      (description "RES - 33 OHM 1% 1/16W - 0402")
      (fields
        (field (name "TOLERANCE") "1%")
        (field (name "PACKAGE") "0402")
        (field (name "Comment") "RC0402FR-0733RL")
        (field (name "CREATEDBY/DATE") "Louis-Daniel Gaulin/ 14/01/2020")
        (field (name "VERIFIEDBY") "C.Paulin - 21/01/2020")
      )
      (libsource (lib "GRAMS_MASTER_LIB") (part "RES_RC0402FR-0733RL"))
    )
    (comp (ref "R175")
      (value "10k")
      (footprint "RES_0402")
      (description "RES - 10K OHMS 1% 1/16W - 0402")
      (fields
        (field (name "TOLERANCE") "1%")
        (field (name "PACKAGE") "0402")
        (field (name "Comment") "RC0402FR-0710KL")
        (field (name "CREATEDBY/DATE") "Nicolas V. (2018-11-20)")
        (field (name "VERIFIEDBY") "Nicolas V. (2018-11-20)")
      )
      (libsource (lib "GRAMS_MASTER_LIB") (part "RES_RC0402FR-0710KL"))
    )
    (comp (ref "R176")
      (value "10k")
      (footprint "RES_0402")
      (description "RES - 10K OHMS 1% 1/16W - 0402")
      (fields
        (field (name "TOLERANCE") "1%")
        (field (name "ASSEMBLY NOTE") "DNI")
        (field (name "PACKAGE") "0402")
        (field (name "Comment") "RC0402FR-0710KL")
        (field (name "CREATEDBY/DATE") "Nicolas V. (2018-11-20)")
        (field (name "VERIFIEDBY") "Nicolas V. (2018-11-20)")
      )
      (libsource (lib "GRAMS_MASTER_LIB") (part "RES_RC0402FR-0710KL"))
    )
    (comp (ref "R178")
      (value "0R")
      (footprint "RES_0402")
      (description "RES - 0R 1/16W 1A  - 0402")
      (fields
        (field (name "PACKAGE") "0402")
        (field (name "Comment") "RC0402FR-070RL")
        (field (name "CREATEDBY/DATE") "Keven Deslandes 2018-09-12")
        (field (name "VERIFIEDBY") "Caroline Paulin - 27 fév 2019")
      )
      (libsource (lib "GRAMS_MASTER_LIB") (part "RES_RC0402FR-070RL"))
    )
    (comp (ref "S3")
      (value "435171014816")
      (footprint "SWI_TACT_435171014816")
      (description "SWI - SWITCH TACTILE SPST-NO 0.05A 12V -SMD")
      (fields
        (field (name "CREATEDBY/DATE") "Hubert Dube - 22/07/20")
        (field (name "VERIFIEDBY") "Louis-Daniel Gaulin / 12-11-2020")
      )
      (libsource (lib "SWARMUS_LIB") (part "SWI_TACT_435171014816"))
    )
    (comp (ref "U1")
      (value "STM32H735ZGT6")
      (footprint "MCU_STM32H735ZGT6")
      (fields
        (field (name "CREATEDBY/DATE") "Philippe Arsenault/2021-04-08")
        (field (name "VERIFIEDBY") "Louis-Daniel Gaulin / 08-04-2021")
      )
      (libsource (lib "SWARMUS_LIB") (part "MCU_STM32H735ZGT6"))
    )
    (comp (ref "X4")
      (value "O 24,0-JO32-B-1V3-1-T1-LF")
      (footprint "OSC_O 24,0-JO32-B-1V3-1-T1-LF")
      (description "OSC - 24MHz XO (Standard) LVCMOS Oscillator 1.8V ~ 3.3V Enable/Disable 4-SMD, No Lead")
      (fields
        (field (name "TOLERANCE") "±50ppm")
        (field (name "CREATEDBY/DATE") "Louis-Daniel Gaulin / 13-04-2021")
        (field (name "VERIFIEDBY") "Philippe Arsenault/2021-04-14")
      )
      (libsource (lib "SWARMUS_LIB") (part "OSC_O 24,0-JO32-B-1V3-1-T1-LF"))
    )
  )
  (nets
    (net (code "1") (name "/CHAN_DET_0A") (class "Default")
      (node (ref "U1") (pin "120") (pinfunction "PD6_120") (pintype "passive"))
    )
    (net (code "2") (name "/CHAN_DET_0B") (class "Default")
      (node (ref "U1") (pin "94") (pinfunction "PC7_94") (pintype "passive"))
    )
    (net (code "3") (name "/CHAN_DET_0C") (class "Default")
      (node (ref "U1") (pin "60") (pinfunction "PE10_60") (pintype "passive"))
    )
    (net (code "4") (name "/CHAN_DET_1A") (class "Default")
      (node (ref "U1") (pin "117") (pinfunction "PD5_117") (pintype "passive"))
    )
    (net (code "5") (name "/CHAN_DET_1B") (class "Default")
      (node (ref "U1") (pin "93") (pinfunction "PC6_93") (pintype "passive"))
    )
    (net (code "6") (name "/CHAN_DET_1C") (class "Default")
      (node (ref "U1") (pin "59") (pinfunction "PE9_59") (pintype "passive"))
    )
    (net (code "7") (name "/CHAN_EN_0A") (class "Default")
      (node (ref "U1") (pin "125") (pinfunction "PG12_125") (pintype "passive"))
    )
    (net (code "8") (name "/CHAN_EN_0B") (class "Default")
      (node (ref "U1") (pin "97") (pinfunction "PA8_97") (pintype "passive"))
    )
    (net (code "9") (name "/CHAN_EN_0C") (class "Default")
      (node (ref "U1") (pin "61") (pinfunction "PE11_61") (pintype "passive"))
    )
    (net (code "10") (name "/CHAN_EN_1A") (class "Default")
      (node (ref "U1") (pin "114") (pinfunction "PD2_114") (pintype "passive"))
    )
    (net (code "11") (name "/CHAN_EN_1B") (class "Default")
      (node (ref "U1") (pin "84") (pinfunction "PD14_84") (pintype "passive"))
    )
    (net (code "12") (name "/CHAN_EN_1C") (class "Default")
      (node (ref "U1") (pin "52") (pinfunction "PF11_52") (pintype "passive"))
    )
    (net (code "13") (name "/CHAN_IRQ_0A") (class "Default")
      (node (ref "U1") (pin "123") (pinfunction "PG10_123") (pintype "passive"))
    )
    (net (code "14") (name "/CHAN_IRQ_0B") (class "Default")
      (node (ref "U1") (pin "95") (pinfunction "PC8_95") (pintype "passive"))
    )
    (net (code "15") (name "/CHAN_IRQ_0C") (class "Default")
      (node (ref "U1") (pin "65") (pinfunction "PE15_65") (pintype "passive"))
    )
    (net (code "16") (name "/CHAN_IRQ_1A") (class "Default")
      (node (ref "U1") (pin "115") (pinfunction "PD3_115") (pintype "passive"))
    )
    (net (code "17") (name "/CHAN_IRQ_1B") (class "Default")
      (node (ref "U1") (pin "82") (pinfunction "PD12_82") (pintype "passive"))
    )
    (net (code "18") (name "/CHAN_IRQ_1C") (class "Default")
      (node (ref "U1") (pin "45") (pinfunction "PA6_45") (pintype "passive"))
    )
    (net (code "19") (name "/CHAN_RESET_0A") (class "Default")
      (node (ref "U1") (pin "113") (pinfunction "PD1_113") (pintype "passive"))
    )
    (net (code "20") (name "/CHAN_RESET_0B") (class "Default")
      (node (ref "U1") (pin "83") (pinfunction "PD13_83") (pintype "passive"))
    )
    (net (code "21") (name "/CHAN_RESET_0C") (class "Default")
      (node (ref "U1") (pin "44") (pinfunction "PA5_44") (pintype "passive"))
    )
    (net (code "22") (name "/CHAN_RESET_1A") (class "Default")
      (node (ref "U1") (pin "112") (pinfunction "PD0_112") (pintype "passive"))
    )
    (net (code "23") (name "/CHAN_RESET_1B") (class "Default")
      (node (ref "U1") (pin "81") (pinfunction "PD11_81") (pintype "passive"))
    )
    (net (code "24") (name "/CHAN_RESET_1C") (class "Default")
      (node (ref "U1") (pin "43") (pinfunction "PA4_43") (pintype "passive"))
    )
    (net (code "25") (name "/CH_CL_PWR_EN") (class "Default")
      (node (ref "U1") (pin "86") (pinfunction "PG6_86") (pintype "passive"))
    )
    (net (code "26") (name "/CLK_OE_0#") (class "Default")
      (node (ref "U1") (pin "88") (pinfunction "PG8_88") (pintype "passive"))
    )
    (net (code "27") (name "/CLK_OE_1#") (class "Default")
      (node (ref "U1") (pin "87") (pinfunction "PG7_87") (pintype "passive"))
    )
    (net (code "28") (name "/DEBUG_EN#") (class "Default")
      (node (ref "U1") (pin "127") (pinfunction "PG14_127") (pintype "passive"))
    )
    (net (code "29") (name "/DEB_PWR_EN") (class "Default")
      (node (ref "U1") (pin "137") (pinfunction "PB9_137") (pintype "passive"))
    )
    (net (code "30") (name "/ETH_PWR_EN") (class "Default")
      (node (ref "U1") (pin "40") (pinfunction "PA3_40") (pintype "passive"))
    )
    (net (code "31") (name "/I2C_MISC_SCL") (class "Default")
      (node (ref "U1") (pin "133") (pinfunction "PB6_133") (pintype "passive"))
    )
    (net (code "32") (name "/I2C_MISC_SDA") (class "Default")
      (node (ref "U1") (pin "134") (pinfunction "PB7_134") (pintype "passive"))
    )
    (net (code "33") (name "/IMU_INT1") (class "Default")
      (node (ref "U1") (pin "9") (pinfunction "PC13_9") (pintype "passive"))
    )
    (net (code "34") (name "/IMU_INT2") (class "Default")
      (node (ref "U1") (pin "3") (pinfunction "PE4_3") (pintype "passive"))
    )
    (net (code "35") (name "/IO_EXP_INT#") (class "Default")
      (node (ref "U1") (pin "4") (pinfunction "PE5_4") (pintype "passive"))
    )
    (net (code "36") (name "/MCU_LED_0") (class "Default")
      (node (ref "D22") (pin "K") (pinfunction "K_K") (pintype "passive"))
      (node (ref "U1") (pin "30") (pinfunction "PC2_C_30") (pintype "passive"))
    )
    (net (code "37") (name "/MCU_LED_1") (class "Default")
      (node (ref "D23") (pin "K") (pinfunction "K_K") (pintype "passive"))
      (node (ref "U1") (pin "28") (pinfunction "PC0_28") (pintype "passive"))
    )
    (net (code "38") (name "/MCU_LED_2") (class "Default")
      (node (ref "D24") (pin "K") (pinfunction "K_K") (pintype "passive"))
      (node (ref "U1") (pin "24") (pinfunction "PF10_24") (pintype "passive"))
    )
    (net (code "39") (name "/MCU_LED_B") (class "Default")
      (node (ref "R1") (pin "2") (pinfunction "2_2") (pintype "passive"))
      (node (ref "U1") (pin "10") (pinfunction "PC14_-_OSC32_IN_10") (pintype "passive"))
    )
    (net (code "40") (name "/MCU_LED_G") (class "Default")
      (node (ref "R2") (pin "2") (pinfunction "2_2") (pintype "passive"))
      (node (ref "U1") (pin "11") (pinfunction "PC15_-_OSC32_OUT_11") (pintype "passive"))
    )
    (net (code "41") (name "/MCU_LED_HB") (class "Default")
      (node (ref "D25") (pin "K") (pinfunction "K_K") (pintype "passive"))
      (node (ref "U1") (pin "31") (pinfunction "PC3_C_31") (pintype "passive"))
    )
    (net (code "42") (name "/MCU_LED_R") (class "Default")
      (node (ref "R3") (pin "2") (pinfunction "2_2") (pintype "passive"))
      (node (ref "U1") (pin "20") (pinfunction "PF6_20") (pintype "passive"))
    )
    (net (code "43") (name "/MCU_OSC_EN") (class "Default")
      (node (ref "R64") (pin "2") (pinfunction "2_2") (pintype "passive"))
      (node (ref "X4") (pin "1") (pinfunction "EN_1") (pintype "passive"))
    )
    (net (code "44") (name "/MCU_RST#") (class "Default")
      (node (ref "R8") (pin "2") (pinfunction "2_2") (pintype "passive"))
      (node (ref "U1") (pin "27") (pinfunction "RST_27") (pintype "passive"))
    )
    (net (code "45") (name "/MEZ_ADC1_N") (class "Default")
      (node (ref "D30") (pin "2") (pinfunction "IO2_2") (pintype "passive"))
      (node (ref "D30") (pin "9") (pinfunction "NC_9") (pintype "passive"))
      (node (ref "J8") (pin "14") (pintype "passive"))
      (node (ref "U1") (pin "49") (pinfunction "PB0_49") (pintype "passive"))
    )
    (net (code "46") (name "/MEZ_ADC1_P") (class "Default")
      (node (ref "D30") (pin "1") (pinfunction "IO1_1") (pintype "passive"))
      (node (ref "D30") (pin "10") (pinfunction "NC_10") (pintype "passive"))
      (node (ref "J8") (pin "12") (pintype "passive"))
      (node (ref "U1") (pin "50") (pinfunction "PB1_50") (pintype "passive"))
    )
    (net (code "47") (name "/MEZ_I2C_SCL") (class "Default")
      (node (ref "D30") (pin "4") (pinfunction "IO3_4") (pintype "passive"))
      (node (ref "D30") (pin "7") (pinfunction "NC_7") (pintype "passive"))
      (node (ref "J8") (pin "13") (pintype "passive"))
      (node (ref "U1") (pin "53") (pinfunction "PF14_53") (pintype "passive"))
    )
    (net (code "48") (name "/MEZ_I2C_SDA") (class "Default")
      (node (ref "D30") (pin "5") (pinfunction "IO4_5") (pintype "passive"))
      (node (ref "D30") (pin "6") (pinfunction "NC_6") (pintype "passive"))
      (node (ref "J8") (pin "15") (pintype "passive"))
      (node (ref "U1") (pin "54") (pinfunction "PF15_54") (pintype "passive"))
    )
    (net (code "49") (name "/MEZ_SPI_MISO") (class "Default")
      (node (ref "D26") (pin "2") (pinfunction "IO2_2") (pintype "passive"))
      (node (ref "D26") (pin "9") (pinfunction "NC_9") (pintype "passive"))
      (node (ref "J8") (pin "7") (pintype "passive"))
      (node (ref "U1") (pin "63") (pinfunction "PE13_63") (pintype "passive"))
    )
    (net (code "50") (name "/MEZ_SPI_MOSI") (class "Default")
      (node (ref "D26") (pin "4") (pinfunction "IO3_4") (pintype "passive"))
      (node (ref "D26") (pin "7") (pinfunction "NC_7") (pintype "passive"))
      (node (ref "J8") (pin "9") (pintype "passive"))
      (node (ref "R173") (pin "2") (pinfunction "2_2") (pintype "passive"))
    )
    (net (code "51") (name "/MEZ_SPI_SCK") (class "Default")
      (node (ref "D26") (pin "1") (pinfunction "IO1_1") (pintype "passive"))
      (node (ref "D26") (pin "10") (pinfunction "NC_10") (pintype "passive"))
      (node (ref "J8") (pin "5") (pintype "passive"))
      (node (ref "R172") (pin "2") (pinfunction "2_2") (pintype "passive"))
    )
    (net (code "52") (name "/MEZ_UART_Rx") (class "Default")
      (node (ref "D29") (pin "1") (pinfunction "IO1_1") (pintype "passive"))
      (node (ref "D29") (pin "10") (pinfunction "NC_10") (pintype "passive"))
      (node (ref "J8") (pin "6") (pintype "passive"))
      (node (ref "U1") (pin "57") (pinfunction "PE7_57") (pintype "passive"))
    )
    (net (code "53") (name "/MEZ_UART_Tx") (class "Default")
      (node (ref "D29") (pin "2") (pinfunction "IO2_2") (pintype "passive"))
      (node (ref "D29") (pin "9") (pinfunction "NC_9") (pintype "passive"))
      (node (ref "J8") (pin "8") (pintype "passive"))
      (node (ref "U1") (pin "58") (pinfunction "PE8_58") (pintype "passive"))
    )
    (net (code "54") (name "/PHY_CRS") (class "Default")
      (node (ref "U1") (pin "46") (pinfunction "PA7_46") (pintype "passive"))
    )
    (net (code "55") (name "/PHY_MAC_CLK") (class "Default")
      (node (ref "U1") (pin "38") (pinfunction "PA1_38") (pintype "passive"))
    )
    (net (code "56") (name "/PHY_MDC") (class "Default")
      (node (ref "U1") (pin "29") (pinfunction "PC1_29") (pintype "passive"))
    )
    (net (code "57") (name "/PHY_MDIO") (class "Default")
      (node (ref "U1") (pin "39") (pinfunction "PA2_39") (pintype "passive"))
    )
    (net (code "58") (name "/PHY_RXD0") (class "Default")
      (node (ref "U1") (pin "47") (pinfunction "PC4_47") (pintype "passive"))
    )
    (net (code "59") (name "/PHY_RXD1") (class "Default")
      (node (ref "U1") (pin "48") (pinfunction "PC5_48") (pintype "passive"))
    )
    (net (code "60") (name "/PHY_TXD0") (class "Default")
      (node (ref "R165") (pin "1") (pinfunction "1_1") (pintype "passive"))
    )
    (net (code "61") (name "/PHY_TXD1") (class "Default")
      (node (ref "R167") (pin "1") (pinfunction "1_1") (pintype "passive"))
    )
    (net (code "62") (name "/PHY_TXEN") (class "Default")
      (node (ref "U1") (pin "67") (pinfunction "PB11_67") (pintype "passive"))
    )
    (net (code "63") (name "/PHY_nRST") (class "Default")
      (node (ref "U1") (pin "37") (pinfunction "PA0_37") (pintype "passive"))
    )
    (net (code "64") (name "/SPI_CLK_A") (class "Default")
      (node (ref "R171") (pin "2") (pinfunction "2_2") (pintype "passive"))
    )
    (net (code "65") (name "/SPI_CLK_B") (class "Default")
      (node (ref "R163") (pin "2") (pinfunction "2_2") (pintype "passive"))
    )
    (net (code "66") (name "/SPI_CLK_C") (class "Default")
      (node (ref "R162") (pin "1") (pinfunction "1_1") (pintype "passive"))
    )
    (net (code "67") (name "/SPI_MISO_A") (class "Default")
      (node (ref "U1") (pin "122") (pinfunction "PG9_122") (pintype "passive"))
    )
    (net (code "68") (name "/SPI_MISO_B") (class "Default")
      (node (ref "U1") (pin "110") (pinfunction "PC11_110") (pintype "passive"))
    )
    (net (code "69") (name "/SPI_MISO_C") (class "Default")
      (node (ref "U1") (pin "74") (pinfunction "PB14_74") (pintype "passive"))
    )
    (net (code "70") (name "/SPI_MOSI_A") (class "Default")
      (node (ref "R161") (pin "1") (pinfunction "1_1") (pintype "passive"))
    )
    (net (code "71") (name "/SPI_MOSI_B") (class "Default")
      (node (ref "R166") (pin "2") (pinfunction "2_2") (pintype "passive"))
    )
    (net (code "72") (name "/SPI_MOSI_C") (class "Default")
      (node (ref "R168") (pin "1") (pinfunction "1_1") (pintype "passive"))
    )
    (net (code "73") (name "/SPI_nCS_0A") (class "Default")
      (node (ref "U1") (pin "126") (pinfunction "PG13_126") (pintype "passive"))
    )
    (net (code "74") (name "/SPI_nCS_0B") (class "Default")
      (node (ref "U1") (pin "96") (pinfunction "PC9_96") (pintype "passive"))
    )
    (net (code "75") (name "/SPI_nCS_0C") (class "Default")
      (node (ref "U1") (pin "51") (pinfunction "PB2_51") (pintype "passive"))
    )
    (net (code "76") (name "/SPI_nCS_1A") (class "Default")
      (node (ref "U1") (pin "116") (pinfunction "PD4_116") (pintype "passive"))
    )
    (net (code "77") (name "/SPI_nCS_1B") (class "Default")
      (node (ref "U1") (pin "85") (pinfunction "PD15_85") (pintype "passive"))
    )
    (net (code "78") (name "/SPI_nCS_1C") (class "Default")
      (node (ref "U1") (pin "78") (pinfunction "PD10_78") (pintype "passive"))
    )
    (net (code "79") (name "/STM_JTCK") (class "Default")
      (node (ref "U1") (pin "107") (pinfunction "PA14_-_JTCK_107") (pintype "passive"))
    )
    (net (code "80") (name "/STM_JTDI") (class "Default")
      (node (ref "U1") (pin "108") (pinfunction "PA15_-_JTDI_108") (pintype "passive"))
    )
    (net (code "81") (name "/STM_JTDO") (class "Default")
      (node (ref "U1") (pin "130") (pinfunction "PB3_-_JTDC_130") (pintype "passive"))
    )
    (net (code "82") (name "/STM_JTMS") (class "Default")
      (node (ref "U1") (pin "102") (pinfunction "PA13_-_JTMS_102") (pintype "passive"))
    )
    (net (code "83") (name "/STM_NJTRST") (class "Default")
      (node (ref "U1") (pin "131") (pinfunction "PB4_-_JTRS_131") (pintype "passive"))
    )
    (net (code "84") (name "/STM_URx") (class "Default")
      (node (ref "U1") (pin "77") (pinfunction "PD9_77") (pintype "passive"))
    )
    (net (code "85") (name "/STM_UTx") (class "Default")
      (node (ref "U1") (pin "76") (pinfunction "PD8_76") (pintype "passive"))
    )
    (net (code "86") (name "/SYNC") (class "Default")
      (node (ref "U1") (pin "99") (pinfunction "PA10_99") (pintype "passive"))
    )
    (net (code "87") (name "/UART2_WROOM_Rx") (class "Default")
      (node (ref "U1") (pin "138") (pinfunction "PE0_138") (pintype "passive"))
    )
    (net (code "88") (name "/UART2_WROOM_Tx") (class "Default")
      (node (ref "U1") (pin "139") (pinfunction "PE1_139") (pintype "passive"))
    )
    (net (code "89") (name "/USB_PWR_DET#") (class "Default")
      (node (ref "U1") (pin "5") (pinfunction "PE6_5") (pintype "passive"))
    )
    (net (code "90") (name "/USB_STM_D_N") (class "Default")
      (node (ref "U1") (pin "100") (pinfunction "PA11_100") (pintype "passive"))
    )
    (net (code "91") (name "/USB_STM_D_P") (class "Default")
      (node (ref "U1") (pin "101") (pinfunction "PA12_101") (pintype "passive"))
    )
    (net (code "92") (name "/USB_STM_VBUS") (class "Default")
      (node (ref "U1") (pin "98") (pinfunction "PA9_98") (pintype "passive"))
    )
    (net (code "93") (name "/VCAP") (class "Default")
      (node (ref "C28") (pin "2") (pinfunction "2_2") (pintype "passive"))
      (node (ref "C29") (pin "2") (pinfunction "2_2") (pintype "passive"))
      (node (ref "C31") (pin "2") (pinfunction "2_2") (pintype "passive"))
      (node (ref "U1") (pin "103") (pinfunction "VCAP_103") (pintype "passive"))
      (node (ref "U1") (pin "140") (pinfunction "VCAP_140") (pintype "passive"))
      (node (ref "U1") (pin "68") (pinfunction "VCAP_68") (pintype "passive"))
    )
    (net (code "94") (name "/VDDA") (class "Default")
      (node (ref "C3") (pin "2") (pinfunction "2_2") (pintype "passive"))
      (node (ref "C6") (pin "1") (pinfunction "1_1") (pintype "passive"))
      (node (ref "L1") (pin "2") (pinfunction "2_2") (pintype "passive"))
      (node (ref "R130") (pin "1") (pinfunction "1_1") (pintype "passive"))
      (node (ref "U1") (pin "36") (pinfunction "VDDA_36") (pintype "passive"))
    )
    (net (code "95") (name "/VDDLDO") (class "Default")
      (node (ref "C20") (pin "2") (pinfunction "2_2") (pintype "passive"))
      (node (ref "C21") (pin "2") (pinfunction "2_2") (pintype "passive"))
      (node (ref "C22") (pin "2") (pinfunction "2_2") (pintype "passive"))
      (node (ref "C23") (pin "2") (pinfunction "2_2") (pintype "passive"))
      (node (ref "C24") (pin "2") (pinfunction "2_2") (pintype "passive"))
      (node (ref "C25") (pin "2") (pinfunction "2_2") (pintype "passive"))
      (node (ref "U1") (pin "105") (pinfunction "VDDLDO_105") (pintype "passive"))
      (node (ref "U1") (pin "143") (pinfunction "VDDLDO_143") (pintype "passive"))
      (node (ref "U1") (pin "70") (pinfunction "VDDLDO_70") (pintype "passive"))
    )
    (net (code "96") (name "/VSPI_CLK") (class "Default")
      (node (ref "R169") (pin "1") (pinfunction "1_1") (pintype "passive"))
    )
    (net (code "97") (name "/VSPI_MISO{slash}Q") (class "Default")
      (node (ref "U1") (pin "22") (pinfunction "PF8_22") (pintype "passive"))
    )
    (net (code "98") (name "/VSPI_MOSI{slash}D") (class "Default")
      (node (ref "R170") (pin "1") (pinfunction "1_1") (pintype "passive"))
    )
    (net (code "99") (name "/VSPI_nCS0") (class "Default")
      (node (ref "U1") (pin "136") (pinfunction "PB8_136") (pintype "passive"))
    )
    (net (code "100") (name "/WROOM_EN") (class "Default")
      (node (ref "U1") (pin "2") (pinfunction "PE3_2") (pintype "passive"))
    )
    (net (code "101") (name "/WROOM_GPIO0") (class "Default")
      (node (ref "U1") (pin "1") (pinfunction "PE2_1") (pintype "passive"))
    )
    (net (code "102") (name "/WR_PWR_EN") (class "Default")
      (node (ref "U1") (pin "132") (pinfunction "PB5_132") (pintype "passive"))
    )
    (net (code "103") (name "3V3") (class "Default")
      (node (ref "C1") (pin "2") (pinfunction "2_2") (pintype "passive"))
      (node (ref "C10") (pin "1") (pinfunction "1_1") (pintype "passive"))
      (node (ref "C11") (pin "2") (pinfunction "2_2") (pintype "passive"))
      (node (ref "C12") (pin "1") (pinfunction "1_1") (pintype "passive"))
      (node (ref "C123") (pin "2") (pinfunction "2_2") (pintype "passive"))
      (node (ref "C13") (pin "1") (pinfunction "1_1") (pintype "passive"))
      (node (ref "C14") (pin "1") (pinfunction "1_1") (pintype "passive"))
      (node (ref "C15") (pin "1") (pinfunction "1_1") (pintype "passive"))
      (node (ref "C16") (pin "1") (pinfunction "1_1") (pintype "passive"))
      (node (ref "C17") (pin "1") (pinfunction "1_1") (pintype "passive"))
      (node (ref "C18") (pin "1") (pinfunction "1_1") (pintype "passive"))
      (node (ref "C19") (pin "1") (pinfunction "1_1") (pintype "passive"))
      (node (ref "C2") (pin "1") (pinfunction "1_1") (pintype "passive"))
      (node (ref "C30") (pin "1") (pinfunction "1_1") (pintype "passive"))
      (node (ref "C5") (pin "2") (pinfunction "2_2") (pintype "passive"))
      (node (ref "C7") (pin "1") (pinfunction "1_1") (pintype "passive"))
      (node (ref "C8") (pin "1") (pinfunction "1_1") (pintype "passive"))
      (node (ref "C9") (pin "1") (pinfunction "1_1") (pintype "passive"))
      (node (ref "D1") (pin "3") (pinfunction "VDD_3") (pintype "passive"))
      (node (ref "D28") (pin "K") (pinfunction "K_K") (pintype "passive"))
      (node (ref "J8") (pin "1") (pintype "passive"))
      (node (ref "L1") (pin "1") (pinfunction "1_1") (pintype "passive"))
      (node (ref "R116") (pin "1") (pinfunction "1_1") (pintype "passive"))
      (node (ref "R129") (pin "1") (pinfunction "1_1") (pintype "passive"))
      (node (ref "R175") (pin "2") (pinfunction "2_2") (pintype "passive"))
      (node (ref "R23") (pin "1") (pinfunction "1_1") (pintype "passive"))
      (node (ref "R33") (pin "1") (pinfunction "1_1") (pintype "passive"))
      (node (ref "R5") (pin "1") (pinfunction "1_1") (pintype "passive"))
      (node (ref "R64") (pin "1") (pinfunction "1_1") (pintype "passive"))
      (node (ref "U1") (pin "106") (pinfunction "VDD_106") (pintype "passive"))
      (node (ref "U1") (pin "119") (pinfunction "VDD_119") (pintype "passive"))
      (node (ref "U1") (pin "129") (pinfunction "VDD_129") (pintype "passive"))
      (node (ref "U1") (pin "13") (pinfunction "VDD_13") (pintype "passive"))
      (node (ref "U1") (pin "144") (pinfunction "VDD_144") (pintype "passive"))
      (node (ref "U1") (pin "19") (pinfunction "VDD_19") (pintype "passive"))
      (node (ref "U1") (pin "32") (pinfunction "VDD_32") (pintype "passive"))
      (node (ref "U1") (pin "42") (pinfunction "VDD_42") (pintype "passive"))
      (node (ref "U1") (pin "56") (pinfunction "VDD_56") (pintype "passive"))
      (node (ref "U1") (pin "7") (pinfunction "VDD_7") (pintype "passive"))
      (node (ref "U1") (pin "71") (pinfunction "VDD_71") (pintype "passive"))
      (node (ref "U1") (pin "79") (pinfunction "VDD_79") (pintype "passive"))
      (node (ref "U1") (pin "8") (pinfunction "VBAT_8") (pintype "passive"))
      (node (ref "U1") (pin "90") (pinfunction "VDD50USB_90") (pintype "passive"))
      (node (ref "U1") (pin "92") (pinfunction "VDD_92") (pintype "passive"))
      (node (ref "X4") (pin "4") (pinfunction "VDC_4") (pintype "passive"))
    )
    (net (code "104") (name "5V") (class "Default")
      (node (ref "D27") (pin "1") (pinfunction "1_1") (pintype "passive"))
      (node (ref "J8") (pin "2") (pintype "passive"))
    )
    (net (code "105") (name "GND") (class "Default")
      (node (ref "C1") (pin "1") (pinfunction "1_1") (pintype "passive"))
      (node (ref "C10") (pin "2") (pinfunction "2_2") (pintype "passive"))
      (node (ref "C11") (pin "1") (pinfunction "1_1") (pintype "passive"))
      (node (ref "C12") (pin "2") (pinfunction "2_2") (pintype "passive"))
      (node (ref "C123") (pin "1") (pinfunction "1_1") (pintype "passive"))
      (node (ref "C13") (pin "2") (pinfunction "2_2") (pintype "passive"))
      (node (ref "C14") (pin "2") (pinfunction "2_2") (pintype "passive"))
      (node (ref "C15") (pin "2") (pinfunction "2_2") (pintype "passive"))
      (node (ref "C16") (pin "2") (pinfunction "2_2") (pintype "passive"))
      (node (ref "C17") (pin "2") (pinfunction "2_2") (pintype "passive"))
      (node (ref "C18") (pin "2") (pinfunction "2_2") (pintype "passive"))
      (node (ref "C19") (pin "2") (pinfunction "2_2") (pintype "passive"))
      (node (ref "C2") (pin "2") (pinfunction "2_2") (pintype "passive"))
      (node (ref "C20") (pin "1") (pinfunction "1_1") (pintype "passive"))
      (node (ref "C21") (pin "1") (pinfunction "1_1") (pintype "passive"))
      (node (ref "C22") (pin "1") (pinfunction "1_1") (pintype "passive"))
      (node (ref "C23") (pin "1") (pinfunction "1_1") (pintype "passive"))
      (node (ref "C24") (pin "1") (pinfunction "1_1") (pintype "passive"))
      (node (ref "C25") (pin "1") (pinfunction "1_1") (pintype "passive"))
      (node (ref "C28") (pin "1") (pinfunction "1_1") (pintype "passive"))
      (node (ref "C29") (pin "1") (pinfunction "1_1") (pintype "passive"))
      (node (ref "C3") (pin "1") (pinfunction "1_1") (pintype "passive"))
      (node (ref "C30") (pin "2") (pinfunction "2_2") (pintype "passive"))
      (node (ref "C31") (pin "1") (pinfunction "1_1") (pintype "passive"))
      (node (ref "C4") (pin "2") (pinfunction "2_2") (pintype "passive"))
      (node (ref "C5") (pin "1") (pinfunction "1_1") (pintype "passive"))
      (node (ref "C6") (pin "2") (pinfunction "2_2") (pintype "passive"))
      (node (ref "C7") (pin "2") (pinfunction "2_2") (pintype "passive"))
      (node (ref "C8") (pin "2") (pinfunction "2_2") (pintype "passive"))
      (node (ref "C9") (pin "2") (pinfunction "2_2") (pintype "passive"))
      (node (ref "D26") (pin "3") (pinfunction "VSS_3") (pintype "passive"))
      (node (ref "D26") (pin "8") (pinfunction "VSS_8") (pintype "passive"))
      (node (ref "D27") (pin "2") (pinfunction "2_2") (pintype "passive"))
      (node (ref "D28") (pin "A") (pinfunction "A_A") (pintype "passive"))
      (node (ref "D29") (pin "3") (pinfunction "VSS_3") (pintype "passive"))
      (node (ref "D29") (pin "8") (pinfunction "VSS_8") (pintype "passive"))
      (node (ref "D30") (pin "3") (pinfunction "VSS_3") (pintype "passive"))
      (node (ref "D30") (pin "8") (pinfunction "VSS_8") (pintype "passive"))
      (node (ref "J8") (pin "10") (pintype "passive"))
      (node (ref "J8") (pin "11") (pintype "passive"))
      (node (ref "J8") (pin "16") (pintype "passive"))
      (node (ref "J8") (pin "3") (pintype "passive"))
      (node (ref "J8") (pin "4") (pintype "passive"))
      (node (ref "MEC1") (pin "1") (pintype "passive"))
      (node (ref "MEC2") (pin "1") (pintype "passive"))
      (node (ref "MTH5") (pin "1") (pinfunction "1_1") (pintype "passive"))
      (node (ref "MTH6") (pin "1") (pinfunction "1_1") (pintype "passive"))
      (node (ref "R122") (pin "2") (pinfunction "2_2") (pintype "passive"))
      (node (ref "R176") (pin "2") (pinfunction "2_2") (pintype "passive"))
      (node (ref "R9") (pin "1") (pinfunction "1_1") (pintype "passive"))
      (node (ref "U1") (pin "104") (pinfunction "VSS_104") (pintype "passive"))
      (node (ref "U1") (pin "118") (pinfunction "VSS_118") (pintype "passive"))
      (node (ref "U1") (pin "12") (pinfunction "VSS_12") (pintype "passive"))
      (node (ref "U1") (pin "128") (pinfunction "VSS_128") (pintype "passive"))
      (node (ref "U1") (pin "14") (pinfunction "VSSSMPS_14") (pintype "passive"))
      (node (ref "U1") (pin "141") (pinfunction "VSS_141") (pintype "passive"))
      (node (ref "U1") (pin "16") (pinfunction "VDDSMPS_16") (pintype "passive"))
      (node (ref "U1") (pin "17") (pinfunction "VFBSMPS_17") (pintype "passive"))
      (node (ref "U1") (pin "18") (pinfunction "VSS_18") (pintype "passive"))
      (node (ref "U1") (pin "33") (pinfunction "VSS_33") (pintype "passive"))
      (node (ref "U1") (pin "34") (pinfunction "VSSA_34") (pintype "passive"))
      (node (ref "U1") (pin "41") (pinfunction "VSS_41") (pintype "passive"))
      (node (ref "U1") (pin "55") (pinfunction "VSS_55") (pintype "passive"))
      (node (ref "U1") (pin "6") (pinfunction "VSS_6") (pintype "passive"))
      (node (ref "U1") (pin "69") (pinfunction "VSS_69") (pintype "passive"))
      (node (ref "U1") (pin "80") (pinfunction "VSS_80") (pintype "passive"))
      (node (ref "U1") (pin "89") (pinfunction "VSS_89") (pintype "passive"))
      (node (ref "U1") (pin "91") (pinfunction "VDD33USB_91") (pintype "passive"))
      (node (ref "X4") (pin "2") (pinfunction "GND_2") (pintype "passive"))
    )
    (net (code "106") (name "Net-(C4-Pad1)") (class "Default")
      (node (ref "C4") (pin "1") (pinfunction "1_1") (pintype "passive"))
      (node (ref "R8") (pin "1") (pinfunction "1_1") (pintype "passive"))
      (node (ref "S3") (pin "3") (pinfunction "3_3") (pintype "passive"))
      (node (ref "S3") (pin "4") (pinfunction "4_4") (pintype "passive"))
    )
    (net (code "107") (name "Net-(D1-B)") (class "Default")
      (node (ref "D1") (pin "1") (pinfunction "B_1") (pintype "passive"))
      (node (ref "R1") (pin "1") (pinfunction "1_1") (pintype "passive"))
    )
    (net (code "108") (name "Net-(D1-G)") (class "Default")
      (node (ref "D1") (pin "2") (pinfunction "G_2") (pintype "passive"))
      (node (ref "R2") (pin "1") (pinfunction "1_1") (pintype "passive"))
    )
    (net (code "109") (name "Net-(D1-R)") (class "Default")
      (node (ref "D1") (pin "4") (pinfunction "R_4") (pintype "passive"))
      (node (ref "R3") (pin "1") (pinfunction "1_1") (pintype "passive"))
    )
    (net (code "110") (name "Net-(D22-PadA)") (class "Default")
      (node (ref "D22") (pin "A") (pinfunction "A_A") (pintype "passive"))
      (node (ref "R5") (pin "2") (pinfunction "2_2") (pintype "passive"))
    )
    (net (code "111") (name "Net-(D23-PadA)") (class "Default")
      (node (ref "D23") (pin "A") (pinfunction "A_A") (pintype "passive"))
      (node (ref "R23") (pin "2") (pinfunction "2_2") (pintype "passive"))
    )
    (net (code "112") (name "Net-(D24-PadA)") (class "Default")
      (node (ref "D24") (pin "A") (pinfunction "A_A") (pintype "passive"))
      (node (ref "R33") (pin "2") (pinfunction "2_2") (pintype "passive"))
    )
    (net (code "113") (name "Net-(D25-PadA)") (class "Default")
      (node (ref "D25") (pin "A") (pinfunction "A_A") (pintype "passive"))
      (node (ref "R129") (pin "2") (pinfunction "2_2") (pintype "passive"))
    )
    (net (code "114") (name "Net-(R9-Pad2)") (class "Default")
      (node (ref "R9") (pin "2") (pinfunction "2_2") (pintype "passive"))
      (node (ref "S3") (pin "1") (pinfunction "1_1") (pintype "passive"))
      (node (ref "S3") (pin "2") (pinfunction "2_2") (pintype "passive"))
    )
    (net (code "115") (name "Net-(U1A-BOOT0)") (class "Default")
      (node (ref "R116") (pin "2") (pinfunction "2_2") (pintype "passive"))
      (node (ref "R122") (pin "1") (pinfunction "1_1") (pintype "passive"))
      (node (ref "U1") (pin "135") (pinfunction "BOOT0_135") (pintype "passive"))
    )
    (net (code "116") (name "Net-(U1A-PDR_ON)") (class "Default")
      (node (ref "R175") (pin "1") (pinfunction "1_1") (pintype "passive"))
      (node (ref "R176") (pin "1") (pinfunction "1_1") (pintype "passive"))
      (node (ref "U1") (pin "142") (pinfunction "PDR_ON_142") (pintype "passive"))
    )
    (net (code "117") (name "Net-(U1A-VREF+)") (class "Default")
      (node (ref "R130") (pin "2") (pinfunction "2_2") (pintype "passive"))
      (node (ref "U1") (pin "35") (pinfunction "VREF+_35") (pintype "passive"))
    )
    (net (code "118") (name "Net-(U1B-PB10)") (class "Default")
      (node (ref "R162") (pin "2") (pinfunction "2_2") (pintype "passive"))
      (node (ref "U1") (pin "66") (pinfunction "PB10_66") (pintype "passive"))
    )
    (net (code "119") (name "Net-(U1B-PB12)") (class "Default")
      (node (ref "R165") (pin "2") (pinfunction "2_2") (pintype "passive"))
      (node (ref "U1") (pin "72") (pinfunction "PB12_72") (pintype "passive"))
    )
    (net (code "120") (name "Net-(U1B-PB13)") (class "Default")
      (node (ref "R167") (pin "2") (pinfunction "2_2") (pintype "passive"))
      (node (ref "U1") (pin "73") (pinfunction "PB13_73") (pintype "passive"))
    )
    (net (code "121") (name "Net-(U1B-PB15)") (class "Default")
      (node (ref "R168") (pin "2") (pinfunction "2_2") (pintype "passive"))
      (node (ref "U1") (pin "75") (pinfunction "PB15_75") (pintype "passive"))
    )
    (net (code "122") (name "Net-(U1C-PC10)") (class "Default")
      (node (ref "R163") (pin "1") (pinfunction "1_1") (pintype "passive"))
      (node (ref "U1") (pin "109") (pinfunction "PC10_109") (pintype "passive"))
    )
    (net (code "123") (name "Net-(U1C-PC12)") (class "Default")
      (node (ref "R166") (pin "1") (pinfunction "1_1") (pintype "passive"))
      (node (ref "U1") (pin "111") (pinfunction "PC12_111") (pintype "passive"))
    )
    (net (code "124") (name "Net-(U1C-PD7)") (class "Default")
      (node (ref "R161") (pin "2") (pinfunction "2_2") (pintype "passive"))
      (node (ref "U1") (pin "121") (pinfunction "PD7_121") (pintype "passive"))
    )
    (net (code "125") (name "Net-(U1D-PE12)") (class "Default")
      (node (ref "R172") (pin "1") (pinfunction "1_1") (pintype "passive"))
      (node (ref "U1") (pin "62") (pinfunction "PE12_62") (pintype "passive"))
    )
    (net (code "126") (name "Net-(U1D-PE14)") (class "Default")
      (node (ref "R173") (pin "1") (pinfunction "1_1") (pintype "passive"))
      (node (ref "U1") (pin "64") (pinfunction "PE14_64") (pintype "passive"))
    )
    (net (code "127") (name "Net-(U1D-PF7)") (class "Default")
      (node (ref "R169") (pin "2") (pinfunction "2_2") (pintype "passive"))
      (node (ref "U1") (pin "21") (pinfunction "PF7_21") (pintype "passive"))
    )
    (net (code "128") (name "Net-(U1D-PF9)") (class "Default")
      (node (ref "R170") (pin "2") (pinfunction "2_2") (pintype "passive"))
      (node (ref "U1") (pin "23") (pinfunction "PF9_23") (pintype "passive"))
    )
    (net (code "129") (name "Net-(U1E-PG11)") (class "Default")
      (node (ref "R171") (pin "1") (pinfunction "1_1") (pintype "passive"))
      (node (ref "U1") (pin "124") (pinfunction "PG11_124") (pintype "passive"))
    )
    (net (code "130") (name "Net-(U1E-PH0-OSC_IN)") (class "Default")
      (node (ref "R178") (pin "2") (pinfunction "2_2") (pintype "passive"))
      (node (ref "U1") (pin "25") (pinfunction "PH0-OSC_IN_25") (pintype "passive"))
    )
    (net (code "131") (name "Net-(X4-OUTPUT)") (class "Default")
      (node (ref "R178") (pin "1") (pinfunction "1_1") (pintype "passive"))
      (node (ref "X4") (pin "3") (pinfunction "OUTPUT_3") (pintype "passive"))
    )
    (net (code "132") (name "unconnected-(D26-IO4-Pad5)") (class "Default")
      (node (ref "D26") (pin "5") (pinfunction "IO4_5") (pintype "passive+no_connect"))
    )
    (net (code "133") (name "unconnected-(D26-NC-Pad6)") (class "Default")
      (node (ref "D26") (pin "6") (pinfunction "NC_6") (pintype "passive+no_connect"))
    )
    (net (code "134") (name "unconnected-(D29-IO3-Pad4)") (class "Default")
      (node (ref "D29") (pin "4") (pinfunction "IO3_4") (pintype "passive+no_connect"))
    )
    (net (code "135") (name "unconnected-(D29-IO4-Pad5)") (class "Default")
      (node (ref "D29") (pin "5") (pinfunction "IO4_5") (pintype "passive+no_connect"))
    )
    (net (code "136") (name "unconnected-(D29-NC-Pad6)") (class "Default")
      (node (ref "D29") (pin "6") (pinfunction "NC_6") (pintype "passive+no_connect"))
    )
    (net (code "137") (name "unconnected-(D29-NC-Pad7)") (class "Default")
      (node (ref "D29") (pin "7") (pinfunction "NC_7") (pintype "passive+no_connect"))
    )
    (net (code "138") (name "unconnected-(U1A-VLXSMPS-Pad15)") (class "Default")
      (node (ref "U1") (pin "15") (pinfunction "VLXSMPS_15") (pintype "passive+no_connect"))
    )
    (net (code "139") (name "unconnected-(U1E-PH0-OSC_OUT-Pad26)") (class "Default")
      (node (ref "U1") (pin "26") (pinfunction "PH0-OSC_OUT_26") (pintype "passive+no_connect"))
    )
  )
)
